# TC_TP2_EJ6.net
KiCad netlist of a schematic drawn in Altium Designer
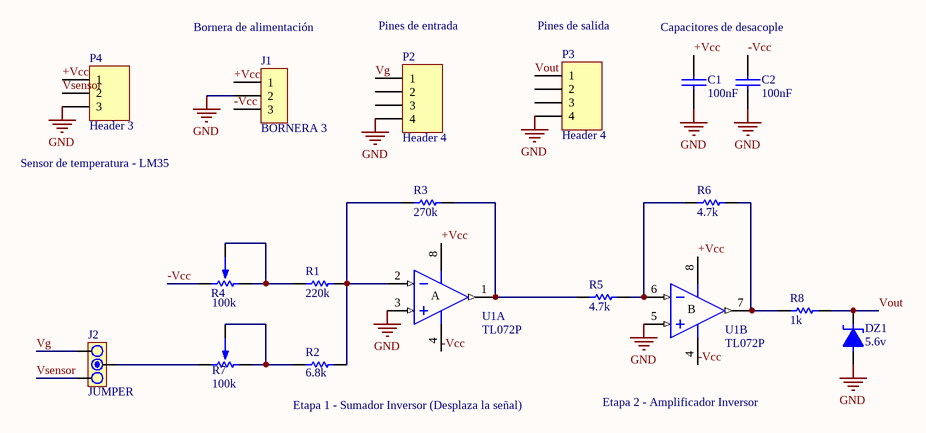
[diagram p0: TC_TP2_EJ6.SchDoc]

(export (version "E")
  (design (tool "Eeschema 10.0.6"))
  (components
    (comp (ref "C1") (value "100nF") (footprint "CAP200") (libsource (lib "LIBEBAL") (part "CAP")))
    (comp (ref "C2") (value "100nF") (footprint "CAP200") (libsource (lib "LIBEBAL") (part "CAP")))
    (comp (ref "DZ1") (value "5.6v") (footprint "DO41") (libsource (lib "LIBEBAL") (part "DIODO ZENER")))
    (comp (ref "J1")
      (value "BORNERA 3")
      (footprint "BORNERA3")
      (libsource (lib "LIBEBAL") (part "BORNERA 3"))
    )
    (comp (ref "J2") (value "JUMPER") (footprint "JUMPER3") (libsource (lib "LIBEBAL") (part "JUMPER3")))
    (comp (ref "P2")
      (value "Header 4")
      (footprint "HDR1X4")
      (description "Header, 4-Pin")
      (fields (field (name "PUBLISHER") "Altium Limited"))
      (libsource (lib "Miscellaneous Connectors") (part "Header 4"))
    )
    (comp (ref "P3")
      (value "Header 4")
      (footprint "HDR1X4")
      (description "Header, 4-Pin")
      (fields (field (name "PUBLISHER") "Altium Limited"))
      (libsource (lib "Miscellaneous Connectors") (part "Header 4"))
    )
    (comp (ref "P4")
      (value "Header 3")
      (footprint "HDR1X3")
      (description "Header, 3-Pin")
      (fields (field (name "PUBLISHER") "Altium Limited"))
      (libsource (lib "Miscellaneous Connectors") (part "Header 3"))
    )
    (comp (ref "R1") (value "220k") (footprint "RES400") (libsource (lib "LIBEBAL") (part "RES")))
    (comp (ref "R2") (value "6.8k") (footprint "RES400") (libsource (lib "LIBEBAL") (part "RES")))
    (comp (ref "R3") (value "270k") (footprint "RES400") (libsource (lib "LIBEBAL") (part "RES")))
    (comp (ref "R4") (value "100k") (footprint "PRESET V") (libsource (lib "LIBEBAL") (part "PRESET")))
    (comp (ref "R5") (value "4.7k") (footprint "RES400") (libsource (lib "LIBEBAL") (part "RES")))
    (comp (ref "R6") (value "4.7k") (footprint "RES400") (libsource (lib "LIBEBAL") (part "RES")))
    (comp (ref "R7") (value "100k") (footprint "PRESET V") (libsource (lib "LIBEBAL") (part "PRESET")))
    (comp (ref "R8") (value "1k") (footprint "RES400") (libsource (lib "LIBEBAL") (part "RES")))
    (comp (ref "U1")
      (value "TL072P")
      (footprint "P008")
      (description "Low-Noise JFET-Input Operational Amplifier")
      (fields (field (name "PUBLISHER") "Altium Limited"))
      (libsource (lib "TI Operational Amplifier") (part "TL072P"))
    )
  )
  (nets
    (net (code "1") (name "/+Vcc") (class "Default")
      (node (ref "C1") (pin "1") (pinfunction "1_1") (pintype "passive"))
      (node (ref "J1") (pin "1") (pinfunction "1_1") (pintype "passive"))
      (node (ref "P4") (pin "1") (pinfunction "1_1") (pintype "passive"))
      (node (ref "U1") (pin "8") (pinfunction "V+_8") (pintype "power_in"))
    )
    (net (code "2") (name "/-Vcc") (class "Default")
      (node (ref "C2") (pin "1") (pinfunction "1_1") (pintype "passive"))
      (node (ref "J1") (pin "3") (pinfunction "3_3") (pintype "passive"))
      (node (ref "R4") (pin "1") (pinfunction "1_1") (pintype "passive"))
      (node (ref "U1") (pin "4") (pinfunction "V-_4") (pintype "power_in"))
    )
    (net (code "3") (name "/Vg") (class "Default")
      (node (ref "J2") (pin "3") (pinfunction "3_3") (pintype "passive"))
      (node (ref "P2") (pin "1") (pinfunction "1_1") (pintype "passive"))
    )
    (net (code "4") (name "/Vout") (class "Default")
      (node (ref "DZ1") (pin "2") (pinfunction "2_2") (pintype "passive"))
      (node (ref "P3") (pin "1") (pinfunction "1_1") (pintype "passive"))
      (node (ref "R8") (pin "2") (pinfunction "2_2") (pintype "passive"))
    )
    (net (code "5") (name "/Vsensor") (class "Default")
      (node (ref "J2") (pin "1") (pinfunction "1_1") (pintype "passive"))
      (node (ref "P4") (pin "2") (pinfunction "2_2") (pintype "passive"))
    )
    (net (code "6") (name "GND") (class "Default")
      (node (ref "C1") (pin "2") (pinfunction "2_2") (pintype "passive"))
      (node (ref "C2") (pin "2") (pinfunction "2_2") (pintype "passive"))
      (node (ref "DZ1") (pin "1") (pinfunction "1_1") (pintype "passive"))
      (node (ref "J1") (pin "2") (pinfunction "2_2") (pintype "passive"))
      (node (ref "P2") (pin "4") (pinfunction "4_4") (pintype "passive"))
      (node (ref "P3") (pin "4") (pinfunction "4_4") (pintype "passive"))
      (node (ref "P4") (pin "3") (pinfunction "3_3") (pintype "passive"))
      (node (ref "U1") (pin "3") (pinfunction "IN+_3") (pintype "input"))
      (node (ref "U1") (pin "5") (pinfunction "IN+_5") (pintype "input"))
    )
    (net (code "7") (name "Net-(J2-Pad2)") (class "Default")
      (node (ref "J2") (pin "2") (pinfunction "2_2") (pintype "passive"))
      (node (ref "R7") (pin "1") (pinfunction "1_1") (pintype "passive"))
    )
    (net (code "8") (name "Net-(R1-Pad1)") (class "Default")
      (node (ref "R1") (pin "1") (pinfunction "1_1") (pintype "passive"))
      (node (ref "R4") (pin "2") (pinfunction "2_2") (pintype "passive"))
      (node (ref "R4") (pin "3") (pinfunction "3_3") (pintype "passive"))
    )
    (net (code "9") (name "Net-(R2-Pad1)") (class "Default")
      (node (ref "R2") (pin "1") (pinfunction "1_1") (pintype "passive"))
      (node (ref "R7") (pin "2") (pinfunction "2_2") (pintype "passive"))
      (node (ref "R7") (pin "3") (pinfunction "3_3") (pintype "passive"))
    )
    (net (code "10") (name "Net-(U1A-IN-)") (class "Default")
      (node (ref "R1") (pin "2") (pinfunction "2_2") (pintype "passive"))
      (node (ref "R2") (pin "2") (pinfunction "2_2") (pintype "passive"))
      (node (ref "R3") (pin "1") (pinfunction "1_1") (pintype "passive"))
      (node (ref "U1") (pin "2") (pinfunction "IN-_2") (pintype "input"))
    )
    (net (code "11") (name "Net-(U1A-OUT)") (class "Default")
      (node (ref "R3") (pin "2") (pinfunction "2_2") (pintype "passive"))
      (node (ref "R5") (pin "1") (pinfunction "1_1") (pintype "passive"))
      (node (ref "U1") (pin "1") (pinfunction "OUT_1") (pintype "output"))
    )
    (net (code "12") (name "Net-(U1B-IN-)") (class "Default")
      (node (ref "R5") (pin "2") (pinfunction "2_2") (pintype "passive"))
      (node (ref "R6") (pin "1") (pinfunction "1_1") (pintype "passive"))
      (node (ref "U1") (pin "6") (pinfunction "IN-_6") (pintype "input"))
    )
    (net (code "13") (name "Net-(U1B-OUT)") (class "Default")
      (node (ref "R6") (pin "2") (pinfunction "2_2") (pintype "passive"))
      (node (ref "R8") (pin "1") (pinfunction "1_1") (pintype "passive"))
      (node (ref "U1") (pin "7") (pinfunction "OUT_7") (pintype "output"))
    )
    (net (code "14") (name "unconnected-(P2-Pad2)") (class "Default")
      (node (ref "P2") (pin "2") (pinfunction "2_2") (pintype "passive"))
    )
    (net (code "15") (name "unconnected-(P2-Pad3)") (class "Default")
      (node (ref "P2") (pin "3") (pinfunction "3_3") (pintype "passive"))
    )
    (net (code "16") (name "unconnected-(P3-Pad2)") (class "Default")
      (node (ref "P3") (pin "2") (pinfunction "2_2") (pintype "passive"))
    )
    (net (code "17") (name "unconnected-(P3-Pad3)") (class "Default")
      (node (ref "P3") (pin "3") (pinfunction "3_3") (pintype "passive"))
    )
  )
)
